# cherrymx1.net
KiCad netlist of a schematic drawn in EAGLE
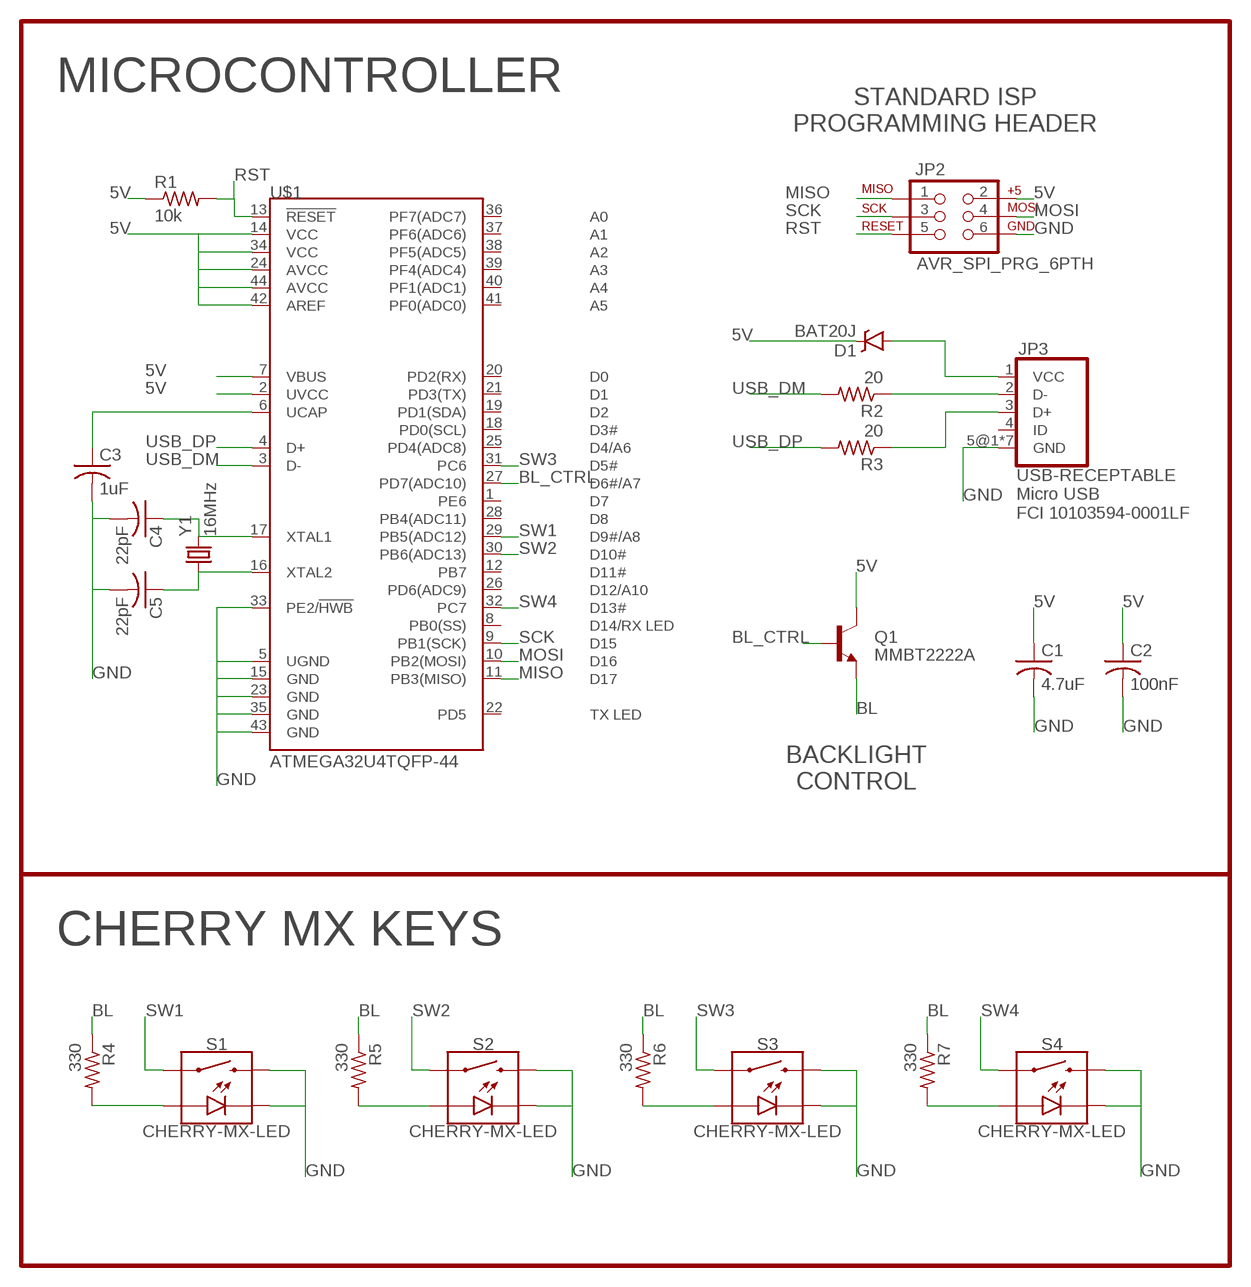
[diagram p0: schematic, sheet 1]

(export (version "E")
  (design (tool "Eeschema 10.0.6"))
  (components
    (comp (ref "C1")
      (value "4.7uF")
      (footprint "eagle-import:C0603")
      (libsource (lib "eagle-import") (part "C-USC0603"))
    )
    (comp (ref "C2")
      (value "100nF")
      (footprint "eagle-import:C0603")
      (libsource (lib "eagle-import") (part "C-USC0603"))
    )
    (comp (ref "C3")
      (value "1uF")
      (footprint "eagle-import:C0603")
      (libsource (lib "eagle-import") (part "C-USC0603"))
    )
    (comp (ref "C4")
      (value "22pF")
      (footprint "eagle-import:C0603")
      (libsource (lib "eagle-import") (part "C-USC0603"))
    )
    (comp (ref "C5")
      (value "22pF")
      (footprint "eagle-import:C0603")
      (libsource (lib "eagle-import") (part "C-USC0603"))
    )
    (comp (ref "D1")
      (value "BAT20J")
      (footprint "eagle-import:SOD-323")
      (libsource (lib "eagle-import") (part "DIODE-SCHOTTKY-BAT20J"))
    )
    (comp (ref "JP2")
      (value "AVR_SPI_PRG_6PTH")
      (footprint "eagle-import:2X3")
      (libsource (lib "eagle-import") (part "AVR_SPI_PRG_6PTH"))
    )
    (comp (ref "JP3")
      (value "USB-RECEPTABLE")
      (footprint "eagle-import:FCI-10103594-0001LF")
      (libsource (lib "eagle-import") (part "USB-RECEPTABLE"))
    )
    (comp (ref "Q1")
      (value "MMBT2222A")
      (footprint "eagle-import:SOT23-3")
      (libsource (lib "eagle-import") (part "TRANSISTOR_NPNMMBT2222A"))
    )
    (comp (ref "R1")
      (value "10k")
      (footprint "eagle-import:R0603")
      (libsource (lib "eagle-import") (part "R-US_R0603"))
    )
    (comp (ref "R2")
      (value "20")
      (footprint "eagle-import:R0603")
      (libsource (lib "eagle-import") (part "R-US_R0603"))
    )
    (comp (ref "R3")
      (value "20")
      (footprint "eagle-import:R0603")
      (libsource (lib "eagle-import") (part "R-US_R0603"))
    )
    (comp (ref "R4")
      (value "330")
      (footprint "eagle-import:R0603")
      (libsource (lib "eagle-import") (part "R-US_R0603"))
    )
    (comp (ref "R5")
      (value "330")
      (footprint "eagle-import:R0603")
      (libsource (lib "eagle-import") (part "R-US_R0603"))
    )
    (comp (ref "R6")
      (value "330")
      (footprint "eagle-import:R0603")
      (libsource (lib "eagle-import") (part "R-US_R0603"))
    )
    (comp (ref "R7")
      (value "330")
      (footprint "eagle-import:R0603")
      (libsource (lib "eagle-import") (part "R-US_R0603"))
    )
    (comp (ref "S1")
      (value "CHERRY-MX-LED")
      (footprint "eagle-import:CHERRY-MX-LED")
      (libsource (lib "eagle-import") (part "CHERRY-MX-LED"))
    )
    (comp (ref "S2")
      (value "CHERRY-MX-LED")
      (footprint "eagle-import:CHERRY-MX-LED")
      (libsource (lib "eagle-import") (part "CHERRY-MX-LED"))
    )
    (comp (ref "S3")
      (value "CHERRY-MX-LED")
      (footprint "eagle-import:CHERRY-MX-LED")
      (libsource (lib "eagle-import") (part "CHERRY-MX-LED"))
    )
    (comp (ref "S4")
      (value "CHERRY-MX-LED")
      (footprint "eagle-import:CHERRY-MX-LED")
      (libsource (lib "eagle-import") (part "CHERRY-MX-LED"))
    )
    (comp (ref "U$1")
      (value "ATMEGA32U4TQFP-44")
      (footprint "eagle-import:TQFP44")
      (libsource (lib "eagle-import") (part "ATMEGA32U4TQFP-44"))
    )
    (comp (ref "Y1")
      (value "16MHz")
      (footprint "eagle-import:CRYSTAL-SMD-5X3")
      (libsource (lib "eagle-import") (part "CRYSTAL5X3"))
    )
  )
  (nets
    (net (code "1") (name "/5V") (class "Default")
      (node (ref "C1") (pin "1") (pinfunction "1_1") (pintype "passive"))
      (node (ref "C2") (pin "1") (pinfunction "1_1") (pintype "passive"))
      (node (ref "D1") (pin "C") (pinfunction "C_C") (pintype "passive"))
      (node (ref "JP2") (pin "2") (pinfunction "2_2") (pintype "passive"))
      (node (ref "Q1") (pin "3") (pinfunction "C_3") (pintype "passive"))
      (node (ref "R1") (pin "1") (pinfunction "1_1") (pintype "passive"))
      (node (ref "U$1") (pin "14") (pinfunction "VCC_14") (pintype "bidirectional"))
      (node (ref "U$1") (pin "2") (pinfunction "UVCC_2") (pintype "bidirectional"))
      (node (ref "U$1") (pin "24") (pinfunction "AVCC_24") (pintype "bidirectional"))
      (node (ref "U$1") (pin "34") (pinfunction "VCC_34") (pintype "bidirectional"))
      (node (ref "U$1") (pin "42") (pinfunction "AREF_42") (pintype "bidirectional"))
      (node (ref "U$1") (pin "44") (pinfunction "AVCC_44") (pintype "bidirectional"))
      (node (ref "U$1") (pin "7") (pinfunction "VBUS_7") (pintype "bidirectional"))
    )
    (net (code "2") (name "/BL") (class "Default")
      (node (ref "Q1") (pin "2") (pinfunction "E_2") (pintype "passive"))
      (node (ref "R4") (pin "1") (pinfunction "1_1") (pintype "passive"))
      (node (ref "R5") (pin "1") (pinfunction "1_1") (pintype "passive"))
      (node (ref "R6") (pin "1") (pinfunction "1_1") (pintype "passive"))
      (node (ref "R7") (pin "1") (pinfunction "1_1") (pintype "passive"))
    )
    (net (code "3") (name "/BL_CTRL") (class "Default")
      (node (ref "Q1") (pin "1") (pinfunction "B_1") (pintype "passive"))
      (node (ref "U$1") (pin "27") (pinfunction "PD7(ADC10)_27") (pintype "bidirectional"))
    )
    (net (code "4") (name "/GND") (class "Default")
      (node (ref "C1") (pin "2") (pinfunction "2_2") (pintype "passive"))
      (node (ref "C2") (pin "2") (pinfunction "2_2") (pintype "passive"))
      (node (ref "C3") (pin "2") (pinfunction "2_2") (pintype "passive"))
      (node (ref "C4") (pin "2") (pinfunction "2_2") (pintype "passive"))
      (node (ref "C5") (pin "2") (pinfunction "2_2") (pintype "passive"))
      (node (ref "JP2") (pin "6") (pinfunction "6_6") (pintype "passive"))
      (node (ref "JP3") (pin "5@1") (pinfunction "GND_5@1") (pintype "bidirectional"))
      (node (ref "JP3") (pin "5@2") (pinfunction "GND_5@2") (pintype "bidirectional"))
      (node (ref "JP3") (pin "5@3") (pinfunction "GND_5@3") (pintype "bidirectional"))
      (node (ref "JP3") (pin "5@4") (pinfunction "GND_5@4") (pintype "bidirectional"))
      (node (ref "JP3") (pin "5@5") (pinfunction "GND_5@5") (pintype "bidirectional"))
      (node (ref "JP3") (pin "5@6") (pinfunction "GND_5@6") (pintype "bidirectional"))
      (node (ref "JP3") (pin "5@7") (pinfunction "GND_5@7") (pintype "bidirectional"))
      (node (ref "S1") (pin "K") (pinfunction "C_K") (pintype "passive"))
      (node (ref "S1") (pin "S2") (pinfunction "S2_S2") (pintype "passive"))
      (node (ref "S2") (pin "K") (pinfunction "C_K") (pintype "passive"))
      (node (ref "S2") (pin "S2") (pinfunction "S2_S2") (pintype "passive"))
      (node (ref "S3") (pin "K") (pinfunction "C_K") (pintype "passive"))
      (node (ref "S3") (pin "S2") (pinfunction "S2_S2") (pintype "passive"))
      (node (ref "S4") (pin "K") (pinfunction "C_K") (pintype "passive"))
      (node (ref "S4") (pin "S2") (pinfunction "S2_S2") (pintype "passive"))
      (node (ref "U$1") (pin "15") (pinfunction "GND_15") (pintype "bidirectional"))
      (node (ref "U$1") (pin "23") (pinfunction "GND_23") (pintype "bidirectional"))
      (node (ref "U$1") (pin "33") (pinfunction "PE2/~{HWB}_33") (pintype "bidirectional"))
      (node (ref "U$1") (pin "35") (pinfunction "GND_35") (pintype "bidirectional"))
      (node (ref "U$1") (pin "43") (pinfunction "GND_43") (pintype "bidirectional"))
      (node (ref "U$1") (pin "5") (pinfunction "UGND_5") (pintype "bidirectional"))
    )
    (net (code "5") (name "/MISO") (class "Default")
      (node (ref "JP2") (pin "1") (pinfunction "1_1") (pintype "passive"))
      (node (ref "U$1") (pin "11") (pinfunction "PB3(MISO)_11") (pintype "bidirectional"))
    )
    (net (code "6") (name "/MOSI") (class "Default")
      (node (ref "JP2") (pin "4") (pinfunction "4_4") (pintype "passive"))
      (node (ref "U$1") (pin "10") (pinfunction "PB2(MOSI)_10") (pintype "bidirectional"))
    )
    (net (code "7") (name "/RST") (class "Default")
      (node (ref "JP2") (pin "5") (pinfunction "5_5") (pintype "passive"))
      (node (ref "R1") (pin "2") (pinfunction "2_2") (pintype "passive"))
      (node (ref "U$1") (pin "13") (pinfunction "~{RESET}_13") (pintype "bidirectional"))
    )
    (net (code "8") (name "/SCK") (class "Default")
      (node (ref "JP2") (pin "3") (pinfunction "3_3") (pintype "passive"))
      (node (ref "U$1") (pin "9") (pinfunction "PB1(SCK)_9") (pintype "bidirectional"))
    )
    (net (code "9") (name "/SW1") (class "Default")
      (node (ref "S1") (pin "S1") (pinfunction "S1_S1") (pintype "passive"))
      (node (ref "U$1") (pin "29") (pinfunction "PB5(ADC12)_29") (pintype "bidirectional"))
    )
    (net (code "10") (name "/SW2") (class "Default")
      (node (ref "S2") (pin "S1") (pinfunction "S1_S1") (pintype "passive"))
      (node (ref "U$1") (pin "30") (pinfunction "PB6(ADC13)_30") (pintype "bidirectional"))
    )
    (net (code "11") (name "/SW3") (class "Default")
      (node (ref "S3") (pin "S1") (pinfunction "S1_S1") (pintype "passive"))
      (node (ref "U$1") (pin "31") (pinfunction "PC6_31") (pintype "bidirectional"))
    )
    (net (code "12") (name "/SW4") (class "Default")
      (node (ref "S4") (pin "S1") (pinfunction "S1_S1") (pintype "passive"))
      (node (ref "U$1") (pin "32") (pinfunction "PC7_32") (pintype "bidirectional"))
    )
    (net (code "13") (name "/USB_DM") (class "Default")
      (node (ref "R2") (pin "2") (pinfunction "2_2") (pintype "passive"))
      (node (ref "U$1") (pin "3") (pinfunction "D-_3") (pintype "bidirectional"))
    )
    (net (code "14") (name "/USB_DP") (class "Default")
      (node (ref "R3") (pin "2") (pinfunction "2_2") (pintype "passive"))
      (node (ref "U$1") (pin "4") (pinfunction "D+_4") (pintype "bidirectional"))
    )
    (net (code "15") (name "Net-(JP3-D+)") (class "Default")
      (node (ref "JP3") (pin "3") (pinfunction "D+_3") (pintype "bidirectional"))
      (node (ref "R3") (pin "1") (pinfunction "1_1") (pintype "passive"))
    )
    (net (code "16") (name "Net-(JP3-D-)") (class "Default")
      (node (ref "JP3") (pin "2") (pinfunction "D-_2") (pintype "bidirectional"))
      (node (ref "R2") (pin "1") (pinfunction "1_1") (pintype "passive"))
    )
    (net (code "17") (name "Net-(JP3-VCC)") (class "Default")
      (node (ref "D1") (pin "A") (pinfunction "A_A") (pintype "passive"))
      (node (ref "JP3") (pin "1") (pinfunction "VCC_1") (pintype "bidirectional"))
    )
    (net (code "18") (name "Net-(R4-Pad2)") (class "Default")
      (node (ref "R4") (pin "2") (pinfunction "2_2") (pintype "passive"))
      (node (ref "S1") (pin "A") (pinfunction "A_A") (pintype "passive"))
    )
    (net (code "19") (name "Net-(R5-Pad2)") (class "Default")
      (node (ref "R5") (pin "2") (pinfunction "2_2") (pintype "passive"))
      (node (ref "S2") (pin "A") (pinfunction "A_A") (pintype "passive"))
    )
    (net (code "20") (name "Net-(R6-Pad2)") (class "Default")
      (node (ref "R6") (pin "2") (pinfunction "2_2") (pintype "passive"))
      (node (ref "S3") (pin "A") (pinfunction "A_A") (pintype "passive"))
    )
    (net (code "21") (name "Net-(R7-Pad2)") (class "Default")
      (node (ref "R7") (pin "2") (pinfunction "2_2") (pintype "passive"))
      (node (ref "S4") (pin "A") (pinfunction "A_A") (pintype "passive"))
    )
    (net (code "22") (name "Net-(U$1-UCAP)") (class "Default")
      (node (ref "C3") (pin "1") (pinfunction "1_1") (pintype "passive"))
      (node (ref "U$1") (pin "6") (pinfunction "UCAP_6") (pintype "bidirectional"))
    )
    (net (code "23") (name "Net-(U$1-XTAL1)") (class "Default")
      (node (ref "C4") (pin "1") (pinfunction "1_1") (pintype "passive"))
      (node (ref "U$1") (pin "17") (pinfunction "XTAL1_17") (pintype "bidirectional"))
      (node (ref "Y1") (pin "3") (pinfunction "2_3") (pintype "passive"))
    )
    (net (code "24") (name "Net-(U$1-XTAL2)") (class "Default")
      (node (ref "C5") (pin "1") (pinfunction "1_1") (pintype "passive"))
      (node (ref "U$1") (pin "16") (pinfunction "XTAL2_16") (pintype "bidirectional"))
      (node (ref "Y1") (pin "1") (pinfunction "1_1") (pintype "passive"))
    )
    (net (code "25") (name "unconnected-(JP3-ID-Pad4)") (class "Default")
      (node (ref "JP3") (pin "4") (pinfunction "ID_4") (pintype "bidirectional"))
    )
    (net (code "26") (name "unconnected-(U$1-PB0(SS)-Pad8)") (class "Default")
      (node (ref "U$1") (pin "8") (pinfunction "PB0(SS)_8") (pintype "bidirectional"))
    )
    (net (code "27") (name "unconnected-(U$1-PB4(ADC11)-Pad28)") (class "Default")
      (node (ref "U$1") (pin "28") (pinfunction "PB4(ADC11)_28") (pintype "bidirectional"))
    )
    (net (code "28") (name "unconnected-(U$1-PB7-Pad12)") (class "Default")
      (node (ref "U$1") (pin "12") (pinfunction "PB7_12") (pintype "bidirectional"))
    )
    (net (code "29") (name "unconnected-(U$1-PD0(SCL)-Pad18)") (class "Default")
      (node (ref "U$1") (pin "18") (pinfunction "PD0(SCL)_18") (pintype "bidirectional"))
    )
    (net (code "30") (name "unconnected-(U$1-PD1(SDA)-Pad19)") (class "Default")
      (node (ref "U$1") (pin "19") (pinfunction "PD1(SDA)_19") (pintype "bidirectional"))
    )
    (net (code "31") (name "unconnected-(U$1-PD2(RX)-Pad20)") (class "Default")
      (node (ref "U$1") (pin "20") (pinfunction "PD2(RX)_20") (pintype "bidirectional"))
    )
    (net (code "32") (name "unconnected-(U$1-PD3(TX)-Pad21)") (class "Default")
      (node (ref "U$1") (pin "21") (pinfunction "PD3(TX)_21") (pintype "bidirectional"))
    )
    (net (code "33") (name "unconnected-(U$1-PD4(ADC8)-Pad25)") (class "Default")
      (node (ref "U$1") (pin "25") (pinfunction "PD4(ADC8)_25") (pintype "bidirectional"))
    )
    (net (code "34") (name "unconnected-(U$1-PD5-Pad22)") (class "Default")
      (node (ref "U$1") (pin "22") (pinfunction "PD5_22") (pintype "bidirectional"))
    )
    (net (code "35") (name "unconnected-(U$1-PD6(ADC9)-Pad26)") (class "Default")
      (node (ref "U$1") (pin "26") (pinfunction "PD6(ADC9)_26") (pintype "bidirectional"))
    )
    (net (code "36") (name "unconnected-(U$1-PE6-Pad1)") (class "Default")
      (node (ref "U$1") (pin "1") (pinfunction "PE6_1") (pintype "bidirectional"))
    )
    (net (code "37") (name "unconnected-(U$1-PF0(ADC0)-Pad41)") (class "Default")
      (node (ref "U$1") (pin "41") (pinfunction "PF0(ADC0)_41") (pintype "bidirectional"))
    )
    (net (code "38") (name "unconnected-(U$1-PF1(ADC1)-Pad40)") (class "Default")
      (node (ref "U$1") (pin "40") (pinfunction "PF1(ADC1)_40") (pintype "bidirectional"))
    )
    (net (code "39") (name "unconnected-(U$1-PF4(ADC4)-Pad39)") (class "Default")
      (node (ref "U$1") (pin "39") (pinfunction "PF4(ADC4)_39") (pintype "bidirectional"))
    )
    (net (code "40") (name "unconnected-(U$1-PF5(ADC5)-Pad38)") (class "Default")
      (node (ref "U$1") (pin "38") (pinfunction "PF5(ADC5)_38") (pintype "bidirectional"))
    )
    (net (code "41") (name "unconnected-(U$1-PF6(ADC6)-Pad37)") (class "Default")
      (node (ref "U$1") (pin "37") (pinfunction "PF6(ADC6)_37") (pintype "bidirectional"))
    )
    (net (code "42") (name "unconnected-(U$1-PF7(ADC7)-Pad36)") (class "Default")
      (node (ref "U$1") (pin "36") (pinfunction "PF7(ADC7)_36") (pintype "bidirectional"))
    )
  )
)
